# module_Rn_reg.net
KiCad netlist of a schematic drawn in EAGLE
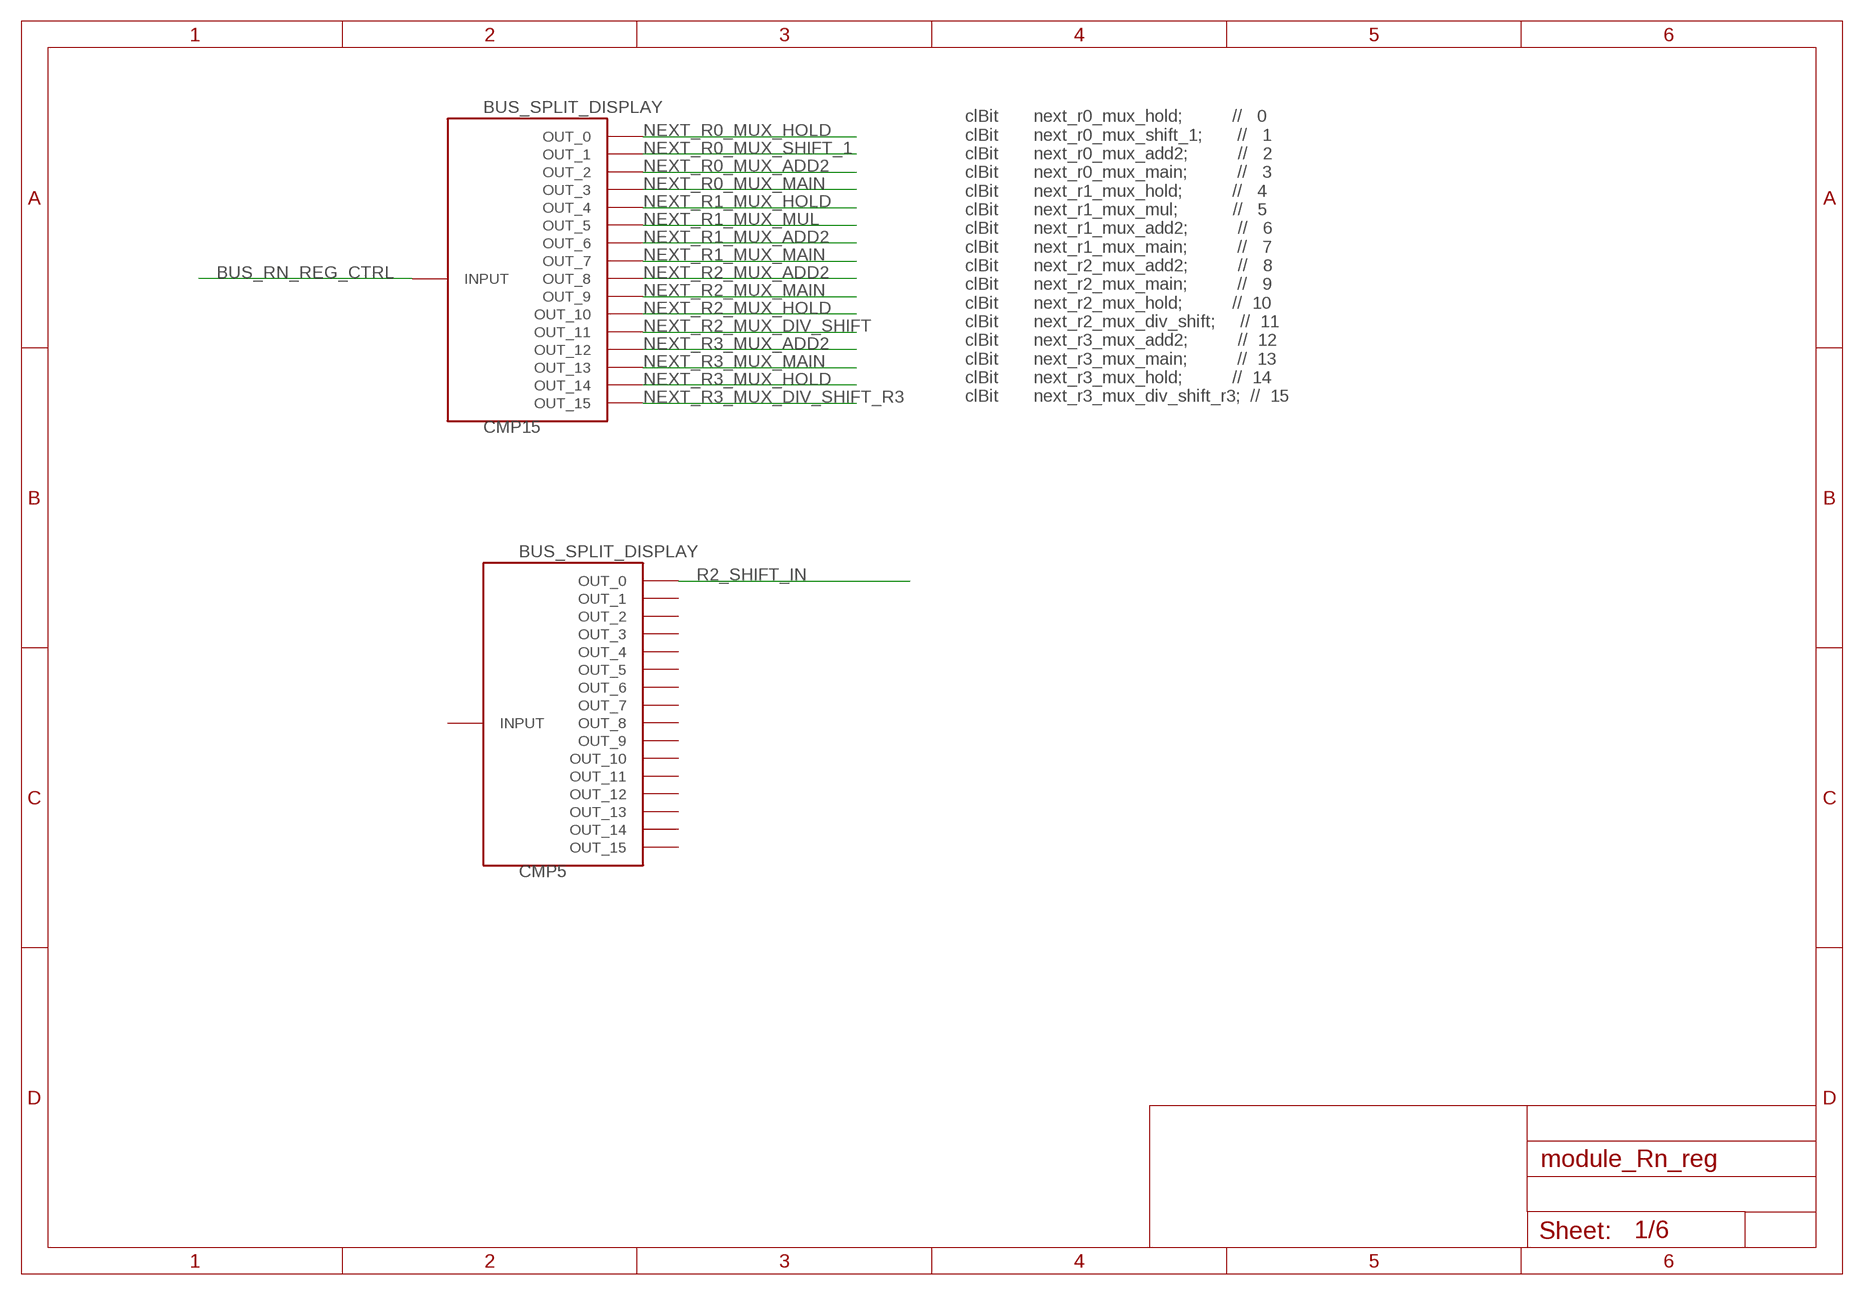
[diagram p0: schematic, sheet 1]
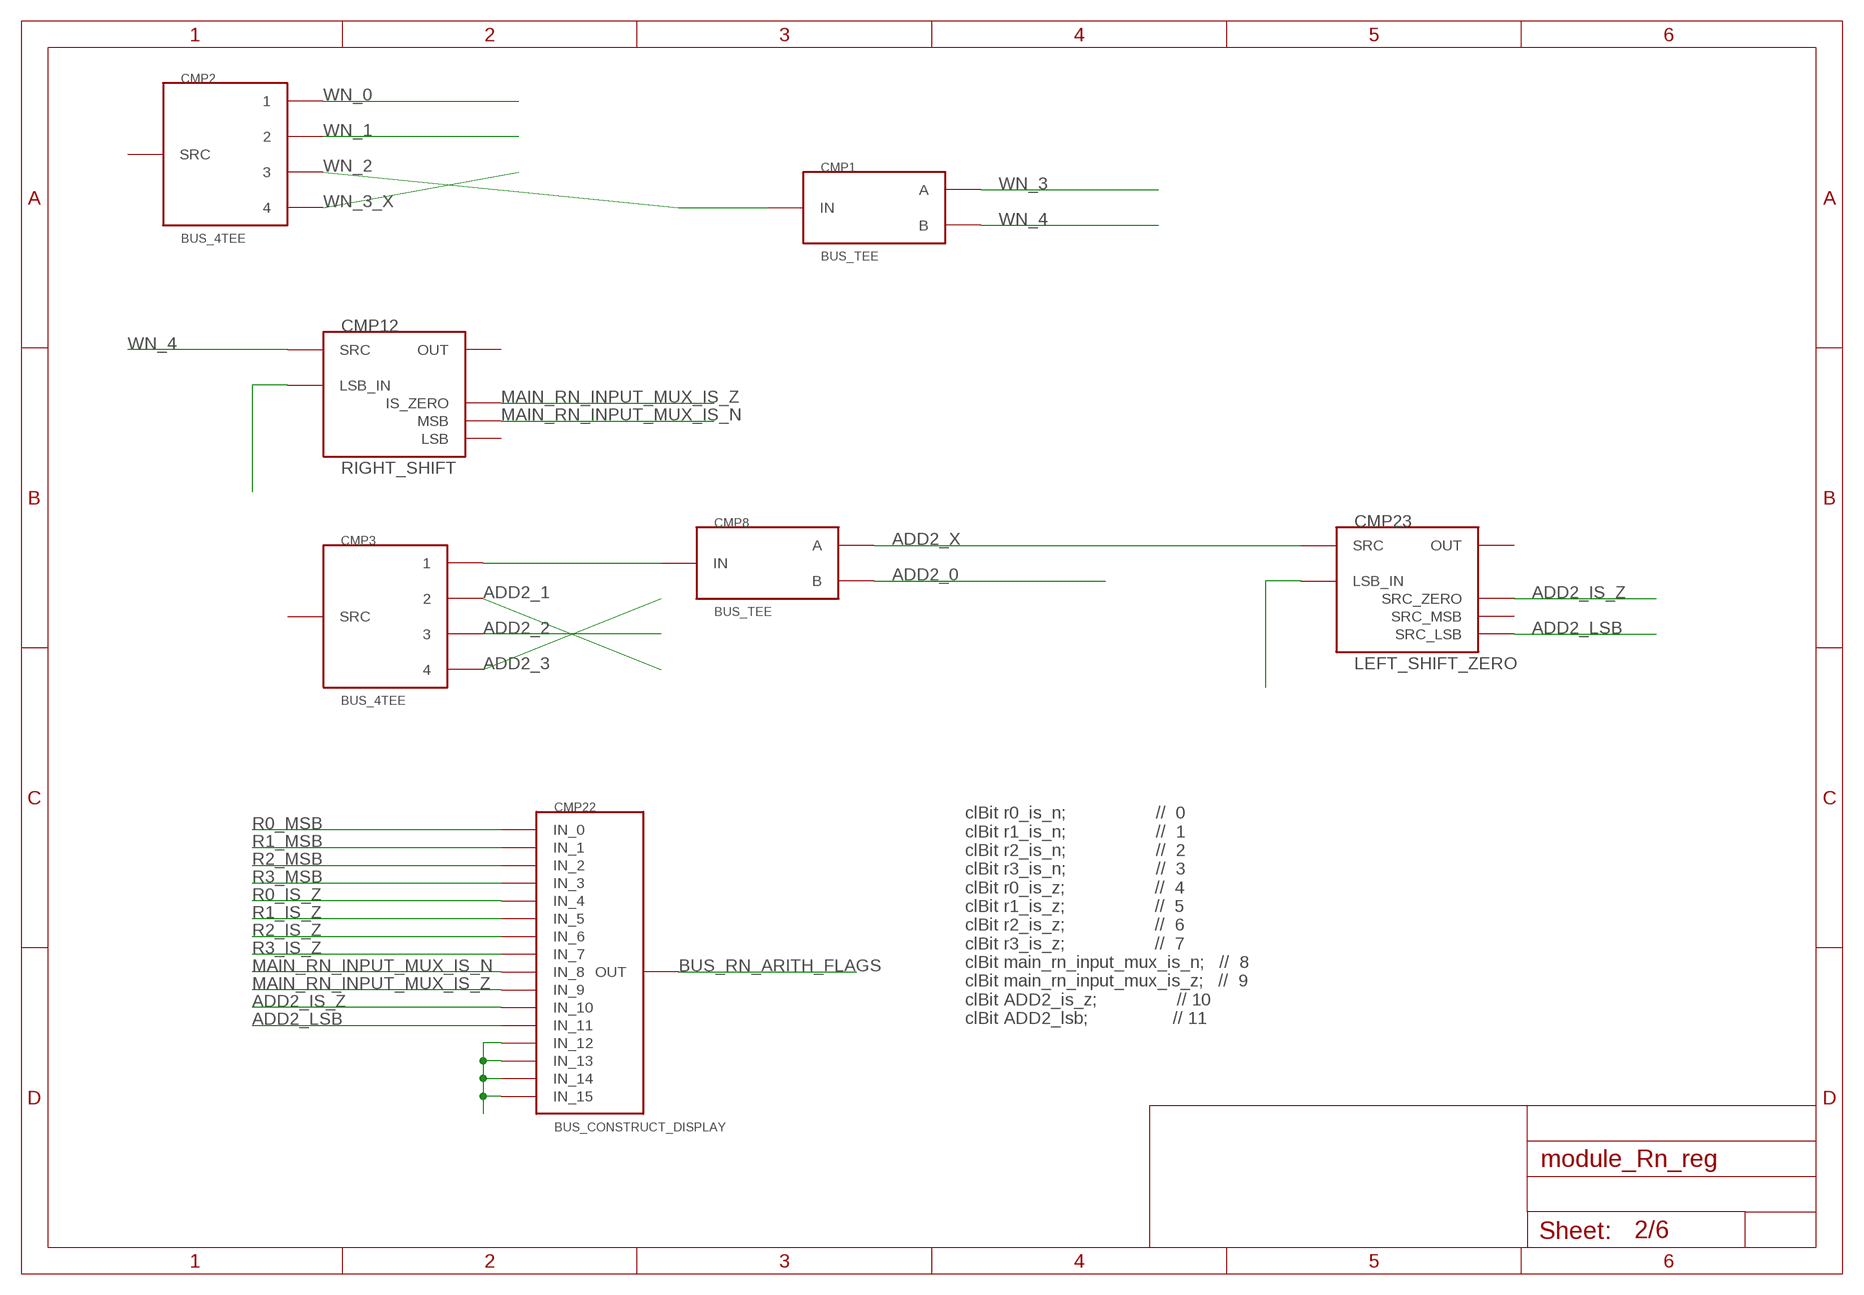
[diagram p1: schematic, sheet 2]
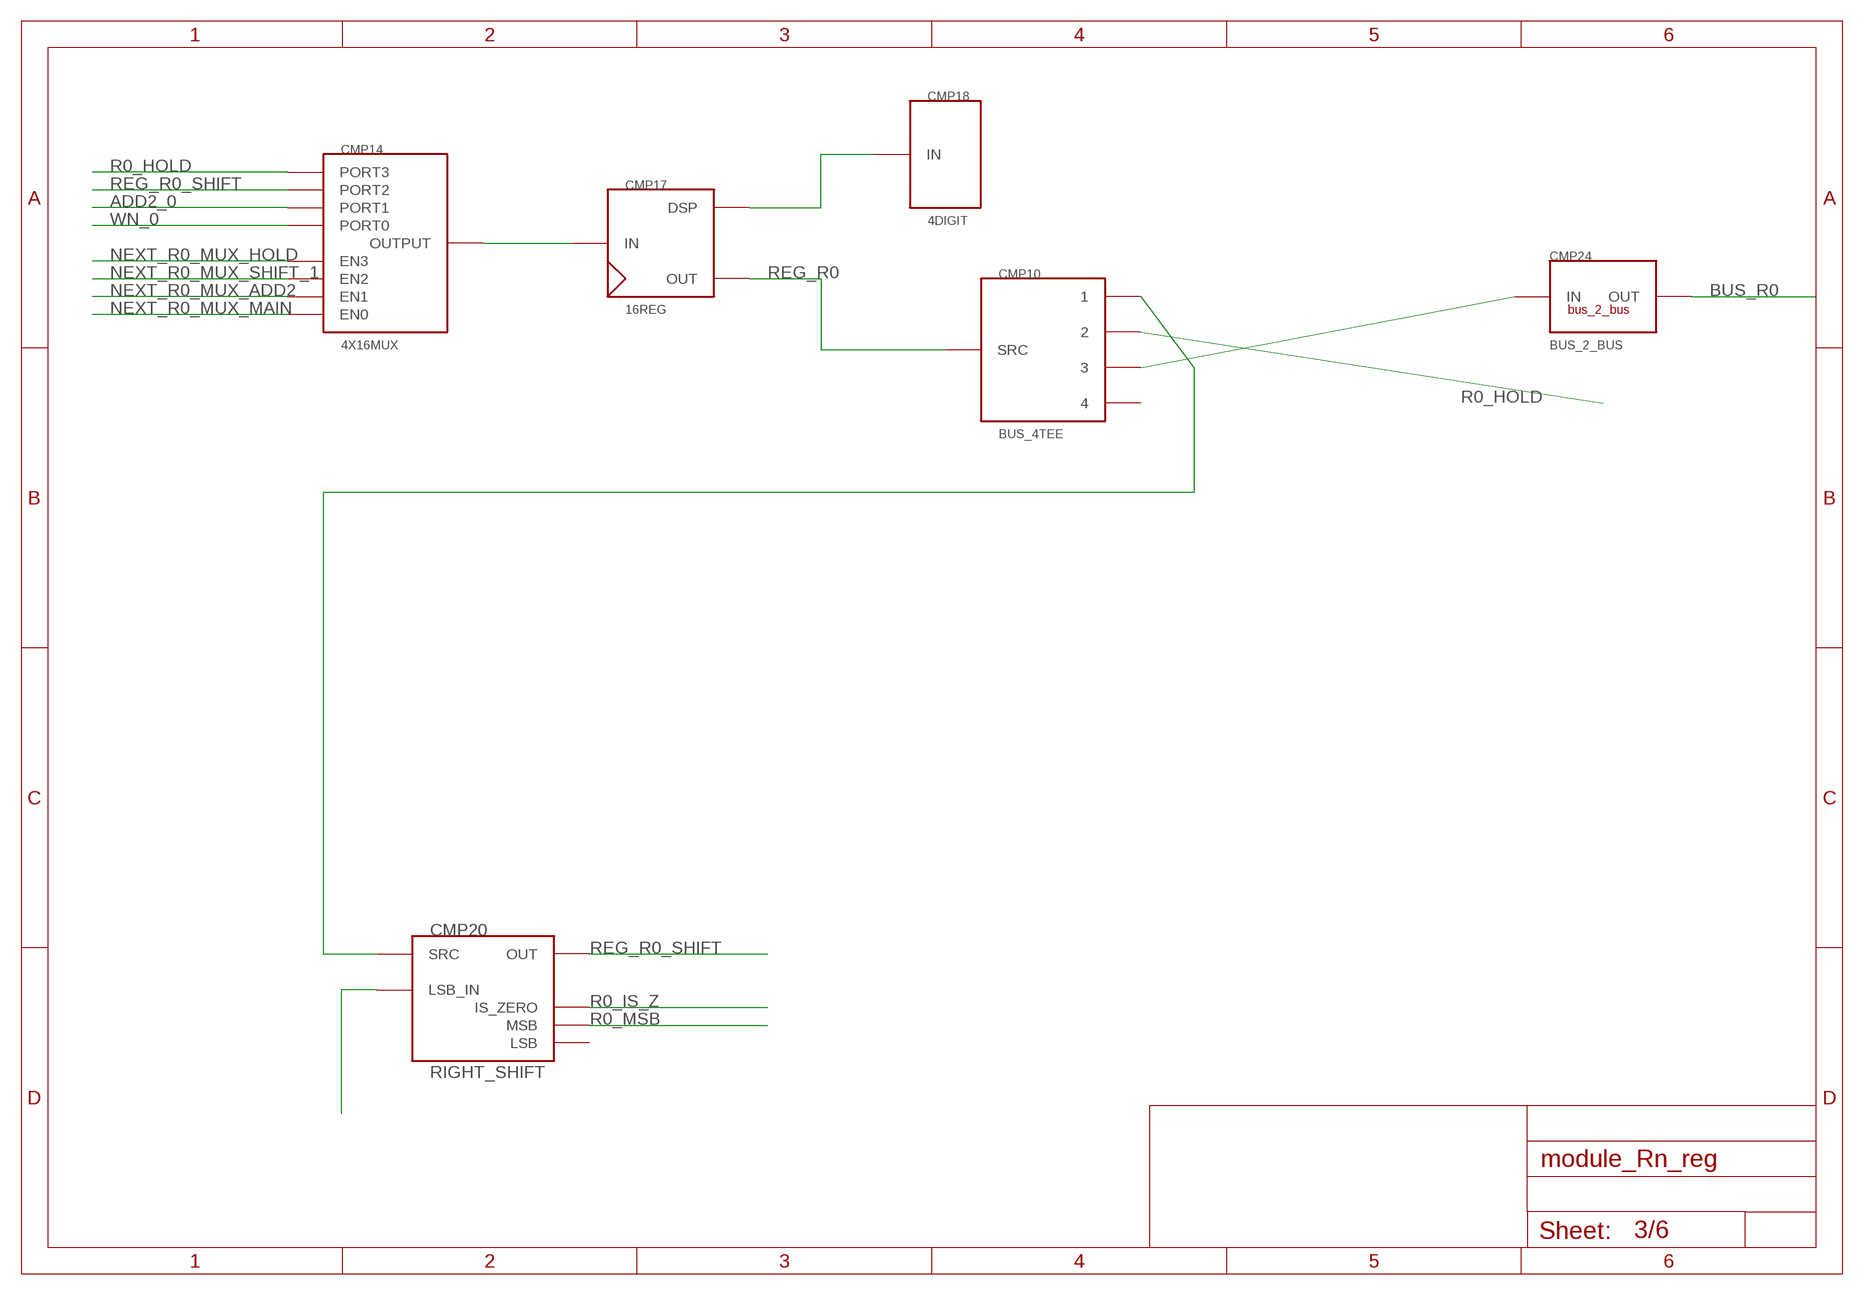
[diagram p2: schematic, sheet 3]
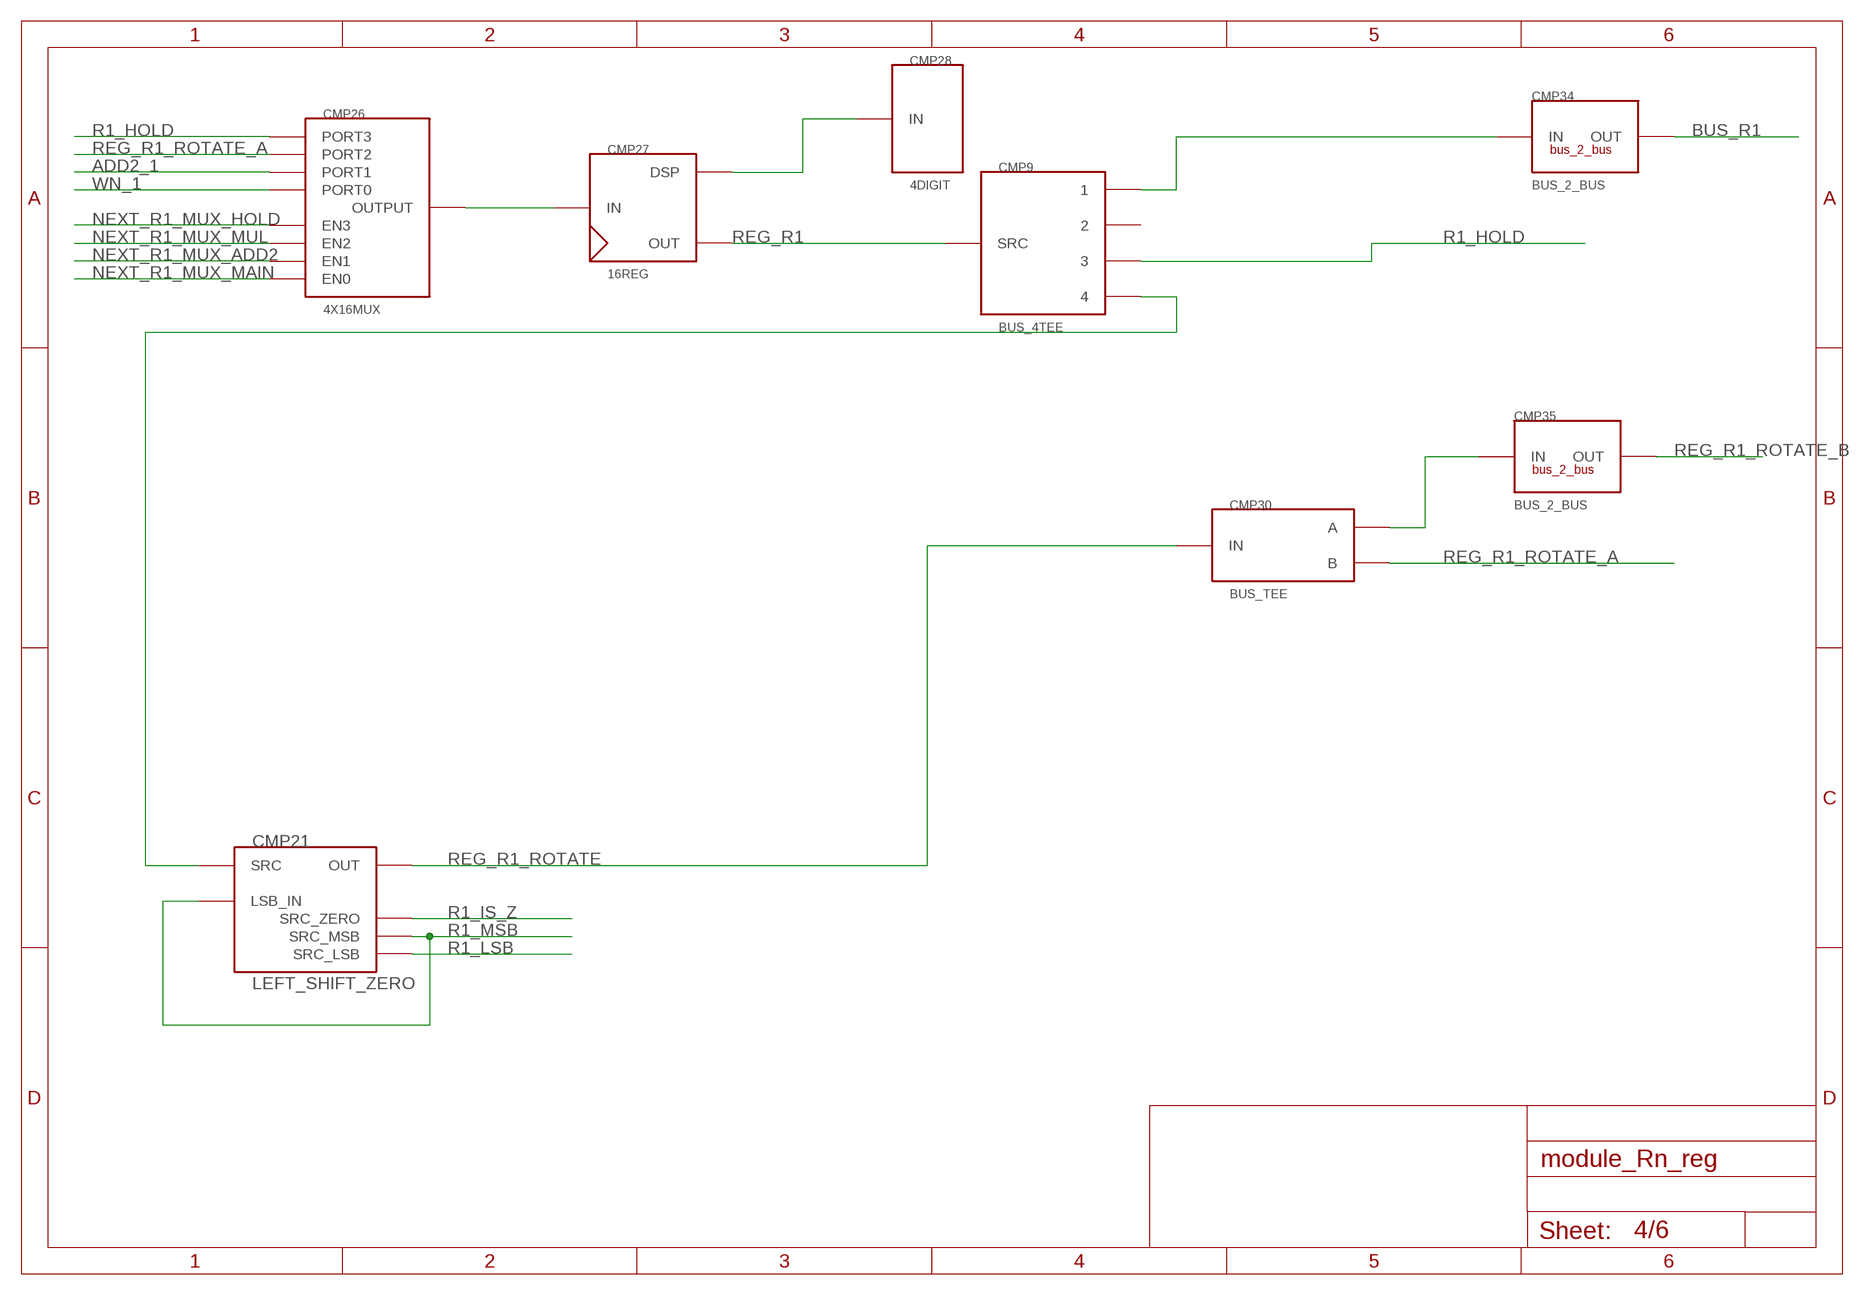
[diagram p3: schematic, sheet 4]
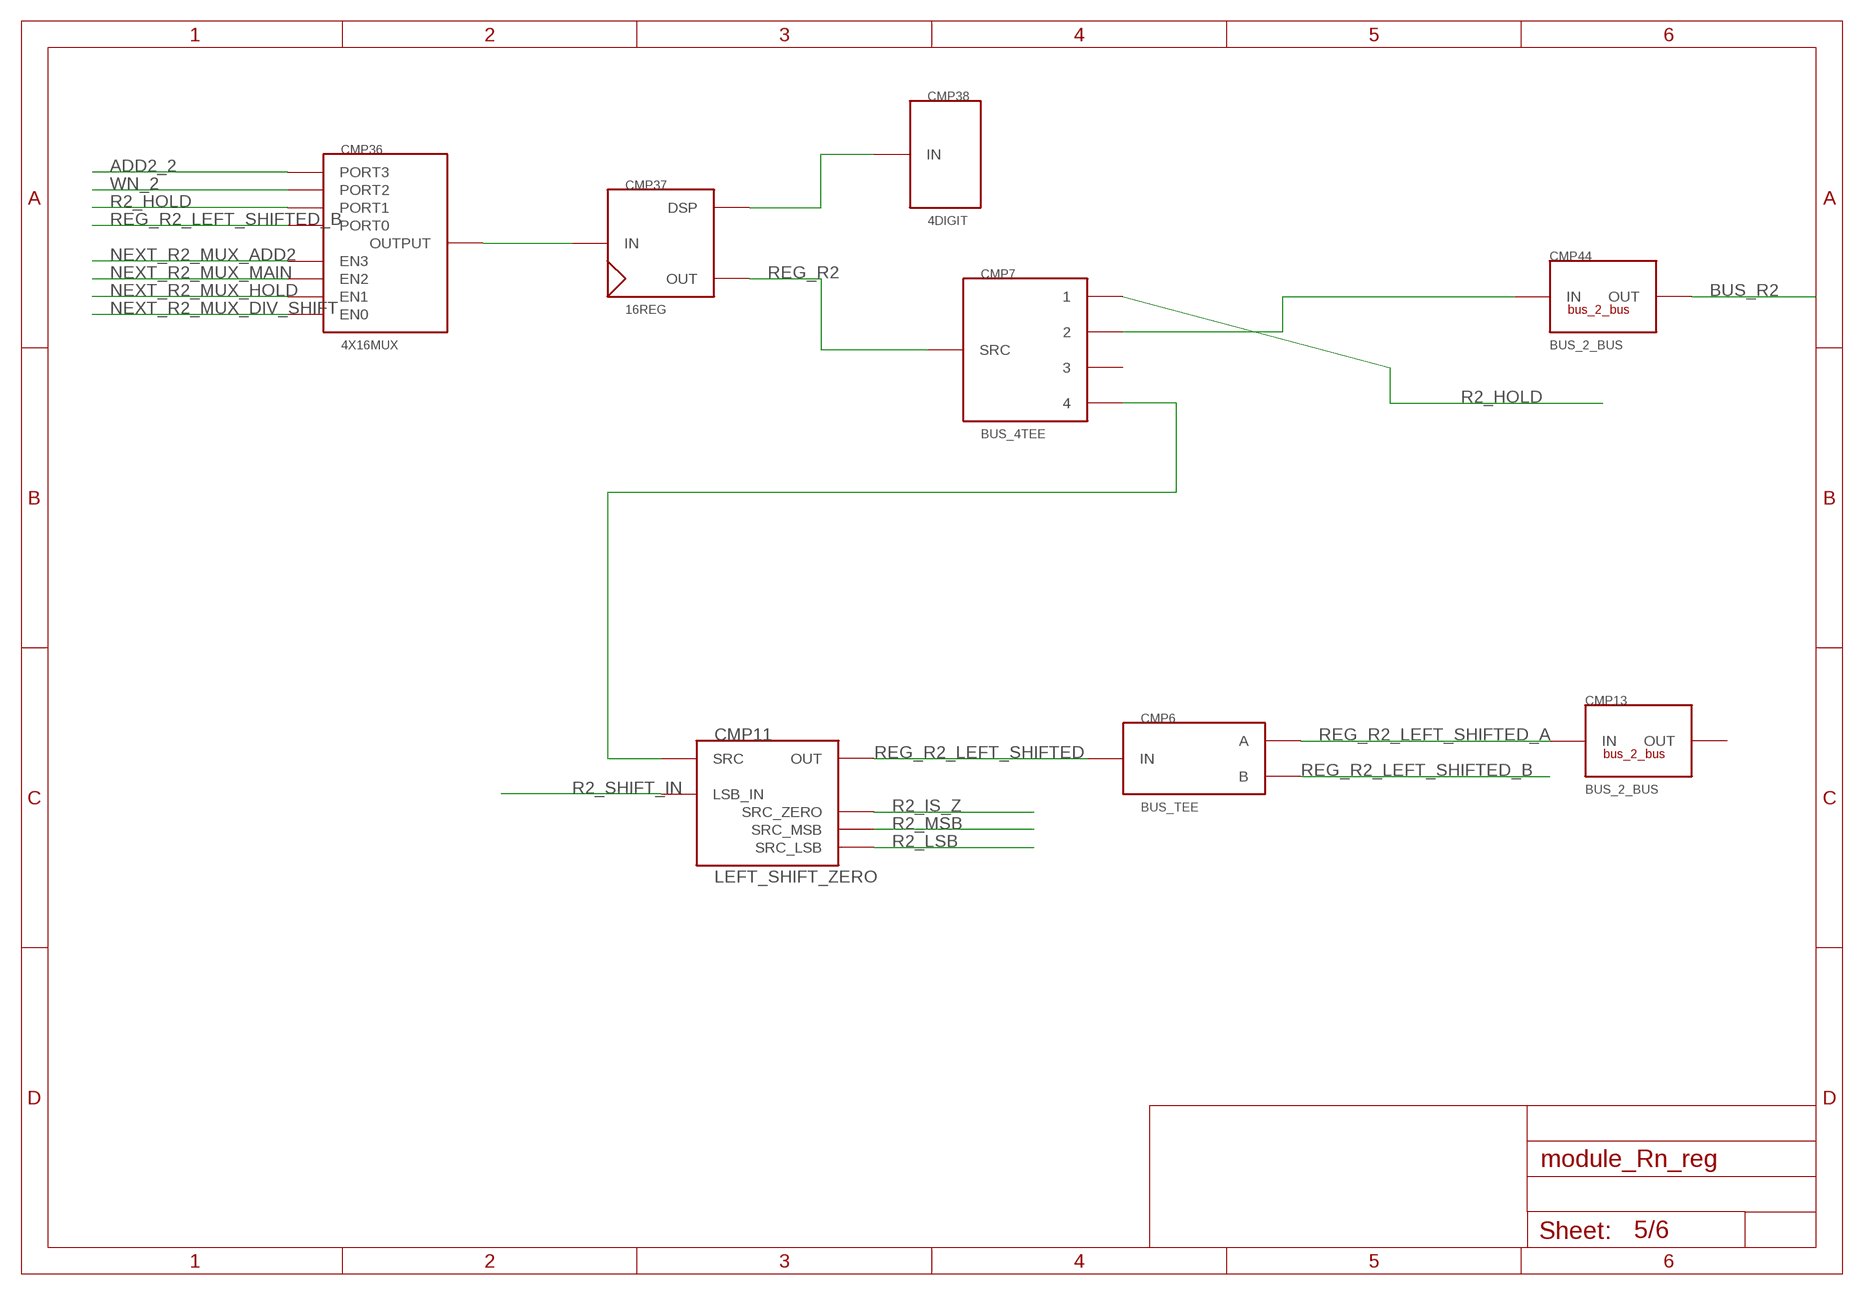
[diagram p4: schematic, sheet 5]
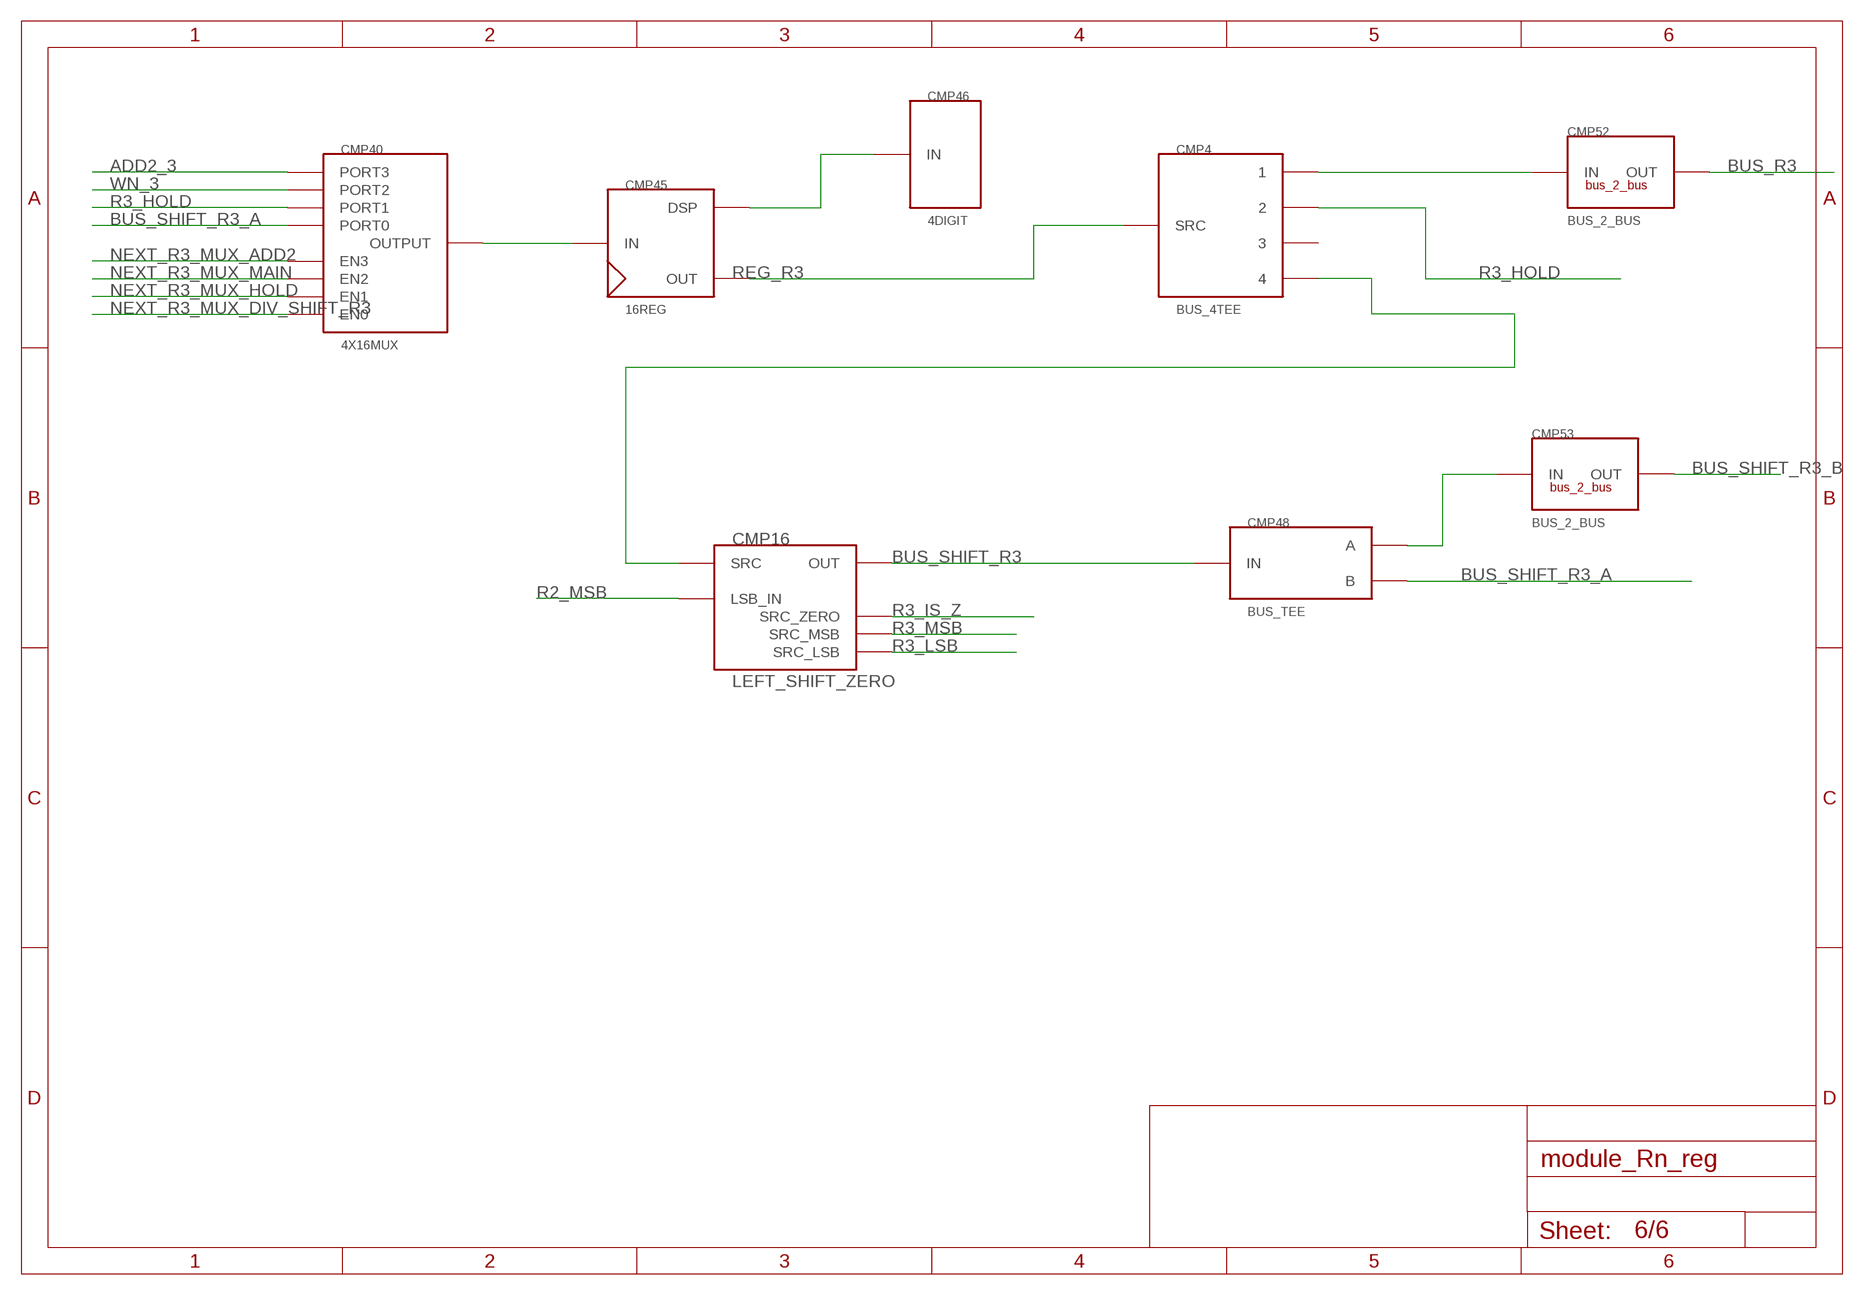
[diagram p5: schematic, sheet 6]

(export (version "E")
  (design (tool "Eeschema 10.0.6"))
  (components
    (comp (ref "CMP1")
      (value "BUS_TEE")
      (footprint "eagle-import:BUS_TEE")
      (libsource (lib "eagle-import") (part "BUS_TEE"))
    )
    (comp (ref "CMP2")
      (value "BUS_4TEE")
      (footprint "eagle-import:BUS_4TEE")
      (libsource (lib "eagle-import") (part "BUS_4TEE"))
    )
    (comp (ref "CMP3")
      (value "BUS_4TEE")
      (footprint "eagle-import:BUS_4TEE")
      (libsource (lib "eagle-import") (part "BUS_4TEE"))
    )
    (comp (ref "CMP8")
      (value "BUS_TEE")
      (footprint "eagle-import:BUS_TEE")
      (libsource (lib "eagle-import") (part "BUS_TEE"))
    )
    (comp (ref "CMP12")
      (value "RIGHT_SHIFT")
      (footprint "eagle-import:SHIFT_ZERO")
      (libsource (lib "eagle-import") (part "RIGHT_SHIFT"))
    )
    (comp (ref "CMP22")
      (value "BUS_CONSTRUCT_DISPLAY")
      (footprint "eagle-import:BUS_SPLIT_DISPLAY")
      (libsource (lib "eagle-import") (part "BUS_CONSTRUCT_DISPLAY"))
    )
    (comp (ref "CMP23")
      (value "LEFT_SHIFT_ZERO")
      (footprint "eagle-import:SHIFT_ZERO")
      (libsource (lib "eagle-import") (part "LEFT_SHIFT_ZERO"))
    )
    (comp (ref "CMP4")
      (value "BUS_4TEE")
      (footprint "eagle-import:BUS_4TEE")
      (libsource (lib "eagle-import") (part "BUS_4TEE"))
    )
    (comp (ref "CMP16")
      (value "LEFT_SHIFT_ZERO")
      (footprint "eagle-import:SHIFT_ZERO")
      (libsource (lib "eagle-import") (part "LEFT_SHIFT_ZERO"))
    )
    (comp (ref "CMP40")
      (value "4X16MUX")
      (footprint "eagle-import:4X16MUX")
      (libsource (lib "eagle-import") (part "4X16MUX"))
    )
    (comp (ref "CMP45")
      (value "16REG")
      (footprint "eagle-import:16REG")
      (libsource (lib "eagle-import") (part "16REG"))
    )
    (comp (ref "CMP46")
      (value "4DIGIT")
      (footprint "eagle-import:4DIGIT")
      (libsource (lib "eagle-import") (part "4DIGIT"))
    )
    (comp (ref "CMP48")
      (value "BUS_TEE")
      (footprint "eagle-import:BUS_TEE")
      (libsource (lib "eagle-import") (part "BUS_TEE"))
    )
    (comp (ref "CMP52")
      (value "BUS_2_BUS")
      (footprint "eagle-import:BUS2BUS")
      (libsource (lib "eagle-import") (part "BUS_2_BUS"))
    )
    (comp (ref "CMP53")
      (value "BUS_2_BUS")
      (footprint "eagle-import:BUS2BUS")
      (libsource (lib "eagle-import") (part "BUS_2_BUS"))
    )
    (comp (ref "CMP9")
      (value "BUS_4TEE")
      (footprint "eagle-import:BUS_4TEE")
      (libsource (lib "eagle-import") (part "BUS_4TEE"))
    )
    (comp (ref "CMP21")
      (value "LEFT_SHIFT_ZERO")
      (footprint "eagle-import:SHIFT_ZERO")
      (libsource (lib "eagle-import") (part "LEFT_SHIFT_ZERO"))
    )
    (comp (ref "CMP26")
      (value "4X16MUX")
      (footprint "eagle-import:4X16MUX")
      (libsource (lib "eagle-import") (part "4X16MUX"))
    )
    (comp (ref "CMP27")
      (value "16REG")
      (footprint "eagle-import:16REG")
      (libsource (lib "eagle-import") (part "16REG"))
    )
    (comp (ref "CMP28")
      (value "4DIGIT")
      (footprint "eagle-import:4DIGIT")
      (libsource (lib "eagle-import") (part "4DIGIT"))
    )
    (comp (ref "CMP30")
      (value "BUS_TEE")
      (footprint "eagle-import:BUS_TEE")
      (libsource (lib "eagle-import") (part "BUS_TEE"))
    )
    (comp (ref "CMP34")
      (value "BUS_2_BUS")
      (footprint "eagle-import:BUS2BUS")
      (libsource (lib "eagle-import") (part "BUS_2_BUS"))
    )
    (comp (ref "CMP35")
      (value "BUS_2_BUS")
      (footprint "eagle-import:BUS2BUS")
      (libsource (lib "eagle-import") (part "BUS_2_BUS"))
    )
    (comp (ref "CMP10")
      (value "BUS_4TEE")
      (footprint "eagle-import:BUS_4TEE")
      (libsource (lib "eagle-import") (part "BUS_4TEE"))
    )
    (comp (ref "CMP14")
      (value "4X16MUX")
      (footprint "eagle-import:4X16MUX")
      (libsource (lib "eagle-import") (part "4X16MUX"))
    )
    (comp (ref "CMP17")
      (value "16REG")
      (footprint "eagle-import:16REG")
      (libsource (lib "eagle-import") (part "16REG"))
    )
    (comp (ref "CMP18")
      (value "4DIGIT")
      (footprint "eagle-import:4DIGIT")
      (libsource (lib "eagle-import") (part "4DIGIT"))
    )
    (comp (ref "CMP20")
      (value "RIGHT_SHIFT")
      (footprint "eagle-import:SHIFT_ZERO")
      (libsource (lib "eagle-import") (part "RIGHT_SHIFT"))
    )
    (comp (ref "CMP24")
      (value "BUS_2_BUS")
      (footprint "eagle-import:BUS2BUS")
      (libsource (lib "eagle-import") (part "BUS_2_BUS"))
    )
    (comp (ref "CMP6")
      (value "BUS_TEE")
      (footprint "eagle-import:BUS_TEE")
      (libsource (lib "eagle-import") (part "BUS_TEE"))
    )
    (comp (ref "CMP7")
      (value "BUS_4TEE")
      (footprint "eagle-import:BUS_4TEE")
      (libsource (lib "eagle-import") (part "BUS_4TEE"))
    )
    (comp (ref "CMP11")
      (value "LEFT_SHIFT_ZERO")
      (footprint "eagle-import:SHIFT_ZERO")
      (libsource (lib "eagle-import") (part "LEFT_SHIFT_ZERO"))
    )
    (comp (ref "CMP13")
      (value "BUS_2_BUS")
      (footprint "eagle-import:BUS2BUS")
      (libsource (lib "eagle-import") (part "BUS_2_BUS"))
    )
    (comp (ref "CMP36")
      (value "4X16MUX")
      (footprint "eagle-import:4X16MUX")
      (libsource (lib "eagle-import") (part "4X16MUX"))
    )
    (comp (ref "CMP37")
      (value "16REG")
      (footprint "eagle-import:16REG")
      (libsource (lib "eagle-import") (part "16REG"))
    )
    (comp (ref "CMP38")
      (value "4DIGIT")
      (footprint "eagle-import:4DIGIT")
      (libsource (lib "eagle-import") (part "4DIGIT"))
    )
    (comp (ref "CMP44")
      (value "BUS_2_BUS")
      (footprint "eagle-import:BUS2BUS")
      (libsource (lib "eagle-import") (part "BUS_2_BUS"))
    )
    (comp (ref "CMP5")
      (value "BUS_SPLIT_DISPLAY")
      (footprint "eagle-import:BUS_SPLIT_DISPLAY")
      (libsource (lib "eagle-import") (part "BUS_SPLIT_DISPLAY"))
    )
    (comp (ref "CMP15")
      (value "BUS_SPLIT_DISPLAY")
      (footprint "eagle-import:BUS_SPLIT_DISPLAY")
      (libsource (lib "eagle-import") (part "BUS_SPLIT_DISPLAY"))
    )
  )
  (nets
    (net (code "1") (name "ADD2_0") (class "Default")
      (node (ref "CMP14") (pin "PORT1") (pinfunction "PORT1_PORT1") (pintype "input"))
      (node (ref "CMP8") (pin "OUTB") (pinfunction "B_OUTB") (pintype "output"))
    )
    (net (code "2") (name "ADD2_1") (class "Default")
      (node (ref "CMP26") (pin "PORT1") (pinfunction "PORT1_PORT1") (pintype "input"))
      (node (ref "CMP3") (pin "4") (pinfunction "4_4") (pintype "output"))
    )
    (net (code "3") (name "ADD2_2") (class "Default")
      (node (ref "CMP3") (pin "3") (pinfunction "3_3") (pintype "output"))
      (node (ref "CMP36") (pin "PORT3") (pinfunction "PORT3_PORT3") (pintype "input"))
    )
    (net (code "4") (name "ADD2_3") (class "Default")
      (node (ref "CMP3") (pin "2") (pinfunction "2_2") (pintype "output"))
      (node (ref "CMP40") (pin "PORT3") (pinfunction "PORT3_PORT3") (pintype "input"))
    )
    (net (code "5") (name "ADD2_IS_Z") (class "Default")
      (node (ref "CMP22") (pin "P$11") (pinfunction "IN_10_P$11") (pintype "input"))
      (node (ref "CMP23") (pin "IS_ZERO") (pinfunction "SRC_ZERO_IS_ZERO") (pintype "output"))
    )
    (net (code "6") (name "ADD2_LSB") (class "Default")
      (node (ref "CMP22") (pin "P$12") (pinfunction "IN_11_P$12") (pintype "input"))
      (node (ref "CMP23") (pin "LSB") (pinfunction "SRC_LSB_LSB") (pintype "output"))
    )
    (net (code "7") (name "ADD2_X") (class "Default")
      (node (ref "CMP23") (pin "LSRC") (pinfunction "SRC_LSRC") (pintype "input"))
      (node (ref "CMP8") (pin "OUT_A") (pinfunction "A_OUT_A") (pintype "output"))
    )
    (net (code "8") (name "BUS_R0") (class "Default")
      (node (ref "CMP24") (pin "P$2") (pinfunction "OUT_P$2") (pintype "output"))
    )
    (net (code "9") (name "BUS_R1") (class "Default")
      (node (ref "CMP34") (pin "P$2") (pinfunction "OUT_P$2") (pintype "output"))
    )
    (net (code "10") (name "BUS_R2") (class "Default")
      (node (ref "CMP44") (pin "P$2") (pinfunction "OUT_P$2") (pintype "output"))
    )
    (net (code "11") (name "BUS_R3") (class "Default")
      (node (ref "CMP52") (pin "P$2") (pinfunction "OUT_P$2") (pintype "output"))
    )
    (net (code "12") (name "BUS_RN_ARITH_FLAGS") (class "Default")
      (node (ref "CMP22") (pin "INPUT") (pinfunction "OUT_INPUT") (pintype "output"))
    )
    (net (code "13") (name "BUS_RN_REG_CTRL") (class "Default")
      (node (ref "CMP15") (pin "INPUT") (pinfunction "INPUT_INPUT") (pintype "input"))
    )
    (net (code "14") (name "BUS_SHIFT_R3") (class "Default")
      (node (ref "CMP16") (pin "RSRC") (pinfunction "OUT_RSRC") (pintype "output"))
      (node (ref "CMP48") (pin "INPUT") (pinfunction "IN_INPUT") (pintype "input"))
    )
    (net (code "15") (name "BUS_SHIFT_R3_A") (class "Default")
      (node (ref "CMP40") (pin "PORT0") (pinfunction "PORT0_PORT0") (pintype "input"))
      (node (ref "CMP48") (pin "OUTB") (pinfunction "B_OUTB") (pintype "output"))
    )
    (net (code "16") (name "BUS_SHIFT_R3_B") (class "Default")
      (node (ref "CMP53") (pin "P$2") (pinfunction "OUT_P$2") (pintype "output"))
    )
    (net (code "17") (name "MAIN_RN_INPUT_MUX_IS_N") (class "Default")
      (node (ref "CMP12") (pin "MSB") (pinfunction "MSB_MSB") (pintype "output"))
      (node (ref "CMP22") (pin "P$9") (pinfunction "IN_8_P$9") (pintype "input"))
    )
    (net (code "18") (name "MAIN_RN_INPUT_MUX_IS_Z") (class "Default")
      (node (ref "CMP12") (pin "IS_ZERO") (pinfunction "IS_ZERO_IS_ZERO") (pintype "output"))
      (node (ref "CMP22") (pin "P$10") (pinfunction "IN_9_P$10") (pintype "input"))
    )
    (net (code "19") (name "NEXT_R0_MUX_ADD2") (class "Default")
      (node (ref "CMP14") (pin "EN1") (pinfunction "EN1_EN1") (pintype "input"))
      (node (ref "CMP15") (pin "P$3") (pinfunction "OUT_2_P$3") (pintype "output"))
    )
    (net (code "20") (name "NEXT_R0_MUX_HOLD") (class "Default")
      (node (ref "CMP14") (pin "EN3") (pinfunction "EN3_EN3") (pintype "input"))
      (node (ref "CMP15") (pin "P$1") (pinfunction "OUT_0_P$1") (pintype "output"))
    )
    (net (code "21") (name "NEXT_R0_MUX_MAIN") (class "Default")
      (node (ref "CMP14") (pin "EN0") (pinfunction "EN0_EN0") (pintype "input"))
      (node (ref "CMP15") (pin "P$4") (pinfunction "OUT_3_P$4") (pintype "output"))
    )
    (net (code "22") (name "NEXT_R0_MUX_SHIFT_1") (class "Default")
      (node (ref "CMP14") (pin "EN2") (pinfunction "EN2_EN2") (pintype "input"))
      (node (ref "CMP15") (pin "P$2") (pinfunction "OUT_1_P$2") (pintype "output"))
    )
    (net (code "23") (name "NEXT_R1_MUX_ADD2") (class "Default")
      (node (ref "CMP15") (pin "P$7") (pinfunction "OUT_6_P$7") (pintype "output"))
      (node (ref "CMP26") (pin "EN1") (pinfunction "EN1_EN1") (pintype "input"))
    )
    (net (code "24") (name "NEXT_R1_MUX_HOLD") (class "Default")
      (node (ref "CMP15") (pin "P$5") (pinfunction "OUT_4_P$5") (pintype "output"))
      (node (ref "CMP26") (pin "EN3") (pinfunction "EN3_EN3") (pintype "input"))
    )
    (net (code "25") (name "NEXT_R1_MUX_MAIN") (class "Default")
      (node (ref "CMP15") (pin "P$8") (pinfunction "OUT_7_P$8") (pintype "output"))
      (node (ref "CMP26") (pin "EN0") (pinfunction "EN0_EN0") (pintype "input"))
    )
    (net (code "26") (name "NEXT_R1_MUX_MUL") (class "Default")
      (node (ref "CMP15") (pin "P$6") (pinfunction "OUT_5_P$6") (pintype "output"))
      (node (ref "CMP26") (pin "EN2") (pinfunction "EN2_EN2") (pintype "input"))
    )
    (net (code "27") (name "NEXT_R2_MUX_ADD2") (class "Default")
      (node (ref "CMP15") (pin "P$9") (pinfunction "OUT_8_P$9") (pintype "output"))
      (node (ref "CMP36") (pin "EN3") (pinfunction "EN3_EN3") (pintype "input"))
    )
    (net (code "28") (name "NEXT_R2_MUX_DIV_SHIFT") (class "Default")
      (node (ref "CMP15") (pin "P$12") (pinfunction "OUT_11_P$12") (pintype "output"))
      (node (ref "CMP36") (pin "EN0") (pinfunction "EN0_EN0") (pintype "input"))
    )
    (net (code "29") (name "NEXT_R2_MUX_HOLD") (class "Default")
      (node (ref "CMP15") (pin "P$11") (pinfunction "OUT_10_P$11") (pintype "output"))
      (node (ref "CMP36") (pin "EN1") (pinfunction "EN1_EN1") (pintype "input"))
    )
    (net (code "30") (name "NEXT_R2_MUX_MAIN") (class "Default")
      (node (ref "CMP15") (pin "P$10") (pinfunction "OUT_9_P$10") (pintype "output"))
      (node (ref "CMP36") (pin "EN2") (pinfunction "EN2_EN2") (pintype "input"))
    )
    (net (code "31") (name "NEXT_R3_MUX_ADD2") (class "Default")
      (node (ref "CMP15") (pin "P$13") (pinfunction "OUT_12_P$13") (pintype "output"))
      (node (ref "CMP40") (pin "EN3") (pinfunction "EN3_EN3") (pintype "input"))
    )
    (net (code "32") (name "NEXT_R3_MUX_DIV_SHIFT_R3") (class "Default")
      (node (ref "CMP15") (pin "P$16") (pinfunction "OUT_15_P$16") (pintype "output"))
      (node (ref "CMP40") (pin "EN0") (pinfunction "EN0_EN0") (pintype "input"))
    )
    (net (code "33") (name "NEXT_R3_MUX_HOLD") (class "Default")
      (node (ref "CMP15") (pin "P$15") (pinfunction "OUT_14_P$15") (pintype "output"))
      (node (ref "CMP40") (pin "EN1") (pinfunction "EN1_EN1") (pintype "input"))
    )
    (net (code "34") (name "NEXT_R3_MUX_MAIN") (class "Default")
      (node (ref "CMP15") (pin "P$14") (pinfunction "OUT_13_P$14") (pintype "output"))
      (node (ref "CMP40") (pin "EN2") (pinfunction "EN2_EN2") (pintype "input"))
    )
    (net (code "35") (name "Net-(CMP8-IN)") (class "Default")
      (node (ref "CMP3") (pin "1") (pinfunction "1_1") (pintype "output"))
      (node (ref "CMP8") (pin "INPUT") (pinfunction "IN_INPUT") (pintype "input"))
    )
    (net (code "36") (name "Net-(CMP11-SRC)") (class "Default")
      (node (ref "CMP11") (pin "LSRC") (pinfunction "SRC_LSRC") (pintype "input"))
      (node (ref "CMP7") (pin "4") (pinfunction "4_4") (pintype "output"))
    )
    (net (code "37") (name "Net-(CMP14-OUTPUT)") (class "Default")
      (node (ref "CMP14") (pin "PORTOUT") (pinfunction "OUTPUT_PORTOUT") (pintype "output"))
      (node (ref "CMP17") (pin "INPUT") (pinfunction "IN_INPUT") (pintype "input"))
    )
    (net (code "38") (name "Net-(CMP16-SRC)") (class "Default")
      (node (ref "CMP16") (pin "LSRC") (pinfunction "SRC_LSRC") (pintype "input"))
      (node (ref "CMP4") (pin "4") (pinfunction "4_4") (pintype "output"))
    )
    (net (code "39") (name "Net-(CMP17-DSP)") (class "Default")
      (node (ref "CMP17") (pin "DISPLAY") (pinfunction "DSP_DISPLAY") (pintype "output"))
      (node (ref "CMP18") (pin "P$1") (pinfunction "IN_P$1") (pintype "input"))
    )
    (net (code "40") (name "Net-(CMP20-SRC)") (class "Default")
      (node (ref "CMP10") (pin "1") (pinfunction "1_1") (pintype "output"))
      (node (ref "CMP20") (pin "RSRC") (pinfunction "SRC_RSRC") (pintype "input"))
    )
    (net (code "41") (name "Net-(CMP21-SRC)") (class "Default")
      (node (ref "CMP21") (pin "LSRC") (pinfunction "SRC_LSRC") (pintype "input"))
      (node (ref "CMP9") (pin "4") (pinfunction "4_4") (pintype "output"))
    )
    (net (code "42") (name "Net-(CMP22-IN_12)") (class "Default")
      (node (ref "CMP22") (pin "P$13") (pinfunction "IN_12_P$13") (pintype "input"))
      (node (ref "CMP22") (pin "P$14") (pinfunction "IN_13_P$14") (pintype "input"))
      (node (ref "CMP22") (pin "P$15") (pinfunction "IN_14_P$15") (pintype "input"))
      (node (ref "CMP22") (pin "P$16") (pinfunction "IN_15_P$16") (pintype "input"))
    )
    (net (code "43") (name "Net-(CMP24-IN)") (class "Default")
      (node (ref "CMP10") (pin "3") (pinfunction "3_3") (pintype "output"))
      (node (ref "CMP24") (pin "P$1") (pinfunction "IN_P$1") (pintype "input"))
    )
    (net (code "44") (name "Net-(CMP26-OUTPUT)") (class "Default")
      (node (ref "CMP26") (pin "PORTOUT") (pinfunction "OUTPUT_PORTOUT") (pintype "output"))
      (node (ref "CMP27") (pin "INPUT") (pinfunction "IN_INPUT") (pintype "input"))
    )
    (net (code "45") (name "Net-(CMP27-DSP)") (class "Default")
      (node (ref "CMP27") (pin "DISPLAY") (pinfunction "DSP_DISPLAY") (pintype "output"))
      (node (ref "CMP28") (pin "P$1") (pinfunction "IN_P$1") (pintype "input"))
    )
    (net (code "46") (name "Net-(CMP30-A)") (class "Default")
      (node (ref "CMP30") (pin "OUT_A") (pinfunction "A_OUT_A") (pintype "output"))
      (node (ref "CMP35") (pin "P$1") (pinfunction "IN_P$1") (pintype "input"))
    )
    (net (code "47") (name "Net-(CMP34-IN)") (class "Default")
      (node (ref "CMP34") (pin "P$1") (pinfunction "IN_P$1") (pintype "input"))
      (node (ref "CMP9") (pin "1") (pinfunction "1_1") (pintype "output"))
    )
    (net (code "48") (name "Net-(CMP36-OUTPUT)") (class "Default")
      (node (ref "CMP36") (pin "PORTOUT") (pinfunction "OUTPUT_PORTOUT") (pintype "output"))
      (node (ref "CMP37") (pin "INPUT") (pinfunction "IN_INPUT") (pintype "input"))
    )
    (net (code "49") (name "Net-(CMP37-DSP)") (class "Default")
      (node (ref "CMP37") (pin "DISPLAY") (pinfunction "DSP_DISPLAY") (pintype "output"))
      (node (ref "CMP38") (pin "P$1") (pinfunction "IN_P$1") (pintype "input"))
    )
    (net (code "50") (name "Net-(CMP40-OUTPUT)") (class "Default")
      (node (ref "CMP40") (pin "PORTOUT") (pinfunction "OUTPUT_PORTOUT") (pintype "output"))
      (node (ref "CMP45") (pin "INPUT") (pinfunction "IN_INPUT") (pintype "input"))
    )
    (net (code "51") (name "Net-(CMP44-IN)") (class "Default")
      (node (ref "CMP44") (pin "P$1") (pinfunction "IN_P$1") (pintype "input"))
      (node (ref "CMP7") (pin "2") (pinfunction "2_2") (pintype "output"))
    )
    (net (code "52") (name "Net-(CMP45-DSP)") (class "Default")
      (node (ref "CMP45") (pin "DISPLAY") (pinfunction "DSP_DISPLAY") (pintype "output"))
      (node (ref "CMP46") (pin "P$1") (pinfunction "IN_P$1") (pintype "input"))
    )
    (net (code "53") (name "Net-(CMP48-A)") (class "Default")
      (node (ref "CMP48") (pin "OUT_A") (pinfunction "A_OUT_A") (pintype "output"))
      (node (ref "CMP53") (pin "P$1") (pinfunction "IN_P$1") (pintype "input"))
    )
    (net (code "54") (name "Net-(CMP52-IN)") (class "Default")
      (node (ref "CMP4") (pin "1") (pinfunction "1_1") (pintype "output"))
      (node (ref "CMP52") (pin "P$1") (pinfunction "IN_P$1") (pintype "input"))
    )
    (net (code "55") (name "R0_HOLD") (class "Default")
      (node (ref "CMP10") (pin "2") (pinfunction "2_2") (pintype "output"))
      (node (ref "CMP14") (pin "PORT3") (pinfunction "PORT3_PORT3") (pintype "input"))
    )
    (net (code "56") (name "R0_IS_Z") (class "Default")
      (node (ref "CMP20") (pin "IS_ZERO") (pinfunction "IS_ZERO_IS_ZERO") (pintype "output"))
      (node (ref "CMP22") (pin "P$5") (pinfunction "IN_4_P$5") (pintype "input"))
    )
    (net (code "57") (name "R0_MSB") (class "Default")
      (node (ref "CMP20") (pin "MSB") (pinfunction "MSB_MSB") (pintype "output"))
      (node (ref "CMP22") (pin "P$1") (pinfunction "IN_0_P$1") (pintype "input"))
    )
    (net (code "58") (name "R1_HOLD") (class "Default")
      (node (ref "CMP26") (pin "PORT3") (pinfunction "PORT3_PORT3") (pintype "input"))
      (node (ref "CMP9") (pin "3") (pinfunction "3_3") (pintype "output"))
    )
    (net (code "59") (name "R1_IS_Z") (class "Default")
      (node (ref "CMP21") (pin "IS_ZERO") (pinfunction "SRC_ZERO_IS_ZERO") (pintype "output"))
      (node (ref "CMP22") (pin "P$6") (pinfunction "IN_5_P$6") (pintype "input"))
    )
    (net (code "60") (name "R1_LSB") (class "Default")
      (node (ref "CMP21") (pin "LSB") (pinfunction "SRC_LSB_LSB") (pintype "output"))
    )
    (net (code "61") (name "R1_MSB") (class "Default")
      (node (ref "CMP21") (pin "MSB") (pinfunction "SRC_MSB_MSB") (pintype "output"))
      (node (ref "CMP21") (pin "SHIFT_IN") (pinfunction "LSB_IN_SHIFT_IN") (pintype "input"))
      (node (ref "CMP22") (pin "P$2") (pinfunction "IN_1_P$2") (pintype "input"))
    )
    (net (code "62") (name "R2_HOLD") (class "Default")
      (node (ref "CMP36") (pin "PORT1") (pinfunction "PORT1_PORT1") (pintype "input"))
      (node (ref "CMP7") (pin "1") (pinfunction "1_1") (pintype "output"))
    )
    (net (code "63") (name "R2_IS_Z") (class "Default")
      (node (ref "CMP11") (pin "IS_ZERO") (pinfunction "SRC_ZERO_IS_ZERO") (pintype "output"))
      (node (ref "CMP22") (pin "P$7") (pinfunction "IN_6_P$7") (pintype "input"))
    )
    (net (code "64") (name "R2_LSB") (class "Default")
      (node (ref "CMP11") (pin "LSB") (pinfunction "SRC_LSB_LSB") (pintype "output"))
    )
    (net (code "65") (name "R2_MSB") (class "Default")
      (node (ref "CMP11") (pin "MSB") (pinfunction "SRC_MSB_MSB") (pintype "output"))
      (node (ref "CMP16") (pin "SHIFT_IN") (pinfunction "LSB_IN_SHIFT_IN") (pintype "input"))
      (node (ref "CMP22") (pin "P$3") (pinfunction "IN_2_P$3") (pintype "input"))
    )
    (net (code "66") (name "R2_SHIFT_IN") (class "Default")
      (node (ref "CMP11") (pin "SHIFT_IN") (pinfunction "LSB_IN_SHIFT_IN") (pintype "input"))
      (node (ref "CMP5") (pin "P$1") (pinfunction "OUT_0_P$1") (pintype "output"))
    )
    (net (code "67") (name "R3_HOLD") (class "Default")
      (node (ref "CMP4") (pin "2") (pinfunction "2_2") (pintype "output"))
      (node (ref "CMP40") (pin "PORT1") (pinfunction "PORT1_PORT1") (pintype "input"))
    )
    (net (code "68") (name "R3_IS_Z") (class "Default")
      (node (ref "CMP16") (pin "IS_ZERO") (pinfunction "SRC_ZERO_IS_ZERO") (pintype "output"))
      (node (ref "CMP22") (pin "P$8") (pinfunction "IN_7_P$8") (pintype "input"))
    )
    (net (code "69") (name "R3_LSB") (class "Default")
      (node (ref "CMP16") (pin "LSB") (pinfunction "SRC_LSB_LSB") (pintype "output"))
    )
    (net (code "70") (name "R3_MSB") (class "Default")
      (node (ref "CMP16") (pin "MSB") (pinfunction "SRC_MSB_MSB") (pintype "output"))
      (node (ref "CMP22") (pin "P$4") (pinfunction "IN_3_P$4") (pintype "input"))
    )
    (net (code "71") (name "REG_R0") (class "Default")
      (node (ref "CMP10") (pin "SRC") (pinfunction "SRC_SRC") (pintype "input"))
      (node (ref "CMP17") (pin "OUT") (pinfunction "OUT_OUT") (pintype "output"))
    )
    (net (code "72") (name "REG_R0_SHIFT") (class "Default")
      (node (ref "CMP14") (pin "PORT2") (pinfunction "PORT2_PORT2") (pintype "input"))
      (node (ref "CMP20") (pin "LSRC") (pinfunction "OUT_LSRC") (pintype "output"))
    )
    (net (code "73") (name "REG_R1") (class "Default")
      (node (ref "CMP27") (pin "OUT") (pinfunction "OUT_OUT") (pintype "output"))
      (node (ref "CMP9") (pin "SRC") (pinfunction "SRC_SRC") (pintype "input"))
    )
    (net (code "74") (name "REG_R1_ROTATE") (class "Default")
      (node (ref "CMP21") (pin "RSRC") (pinfunction "OUT_RSRC") (pintype "output"))
      (node (ref "CMP30") (pin "INPUT") (pinfunction "IN_INPUT") (pintype "input"))
    )
    (net (code "75") (name "REG_R1_ROTATE_A") (class "Default")
      (node (ref "CMP26") (pin "PORT2") (pinfunction "PORT2_PORT2") (pintype "input"))
      (node (ref "CMP30") (pin "OUTB") (pinfunction "B_OUTB") (pintype "output"))
    )
    (net (code "76") (name "REG_R1_ROTATE_B") (class "Default")
      (node (ref "CMP35") (pin "P$2") (pinfunction "OUT_P$2") (pintype "output"))
    )
    (net (code "77") (name "REG_R2") (class "Default")
      (node (ref "CMP37") (pin "OUT") (pinfunction "OUT_OUT") (pintype "output"))
      (node (ref "CMP7") (pin "SRC") (pinfunction "SRC_SRC") (pintype "input"))
    )
    (net (code "78") (name "REG_R2_LEFT_SHIFTED") (class "Default")
      (node (ref "CMP11") (pin "RSRC") (pinfunction "OUT_RSRC") (pintype "output"))
      (node (ref "CMP6") (pin "INPUT") (pinfunction "IN_INPUT") (pintype "input"))
    )
    (net (code "79") (name "REG_R2_LEFT_SHIFTED_A") (class "Default")
      (node (ref "CMP13") (pin "P$1") (pinfunction "IN_P$1") (pintype "input"))
      (node (ref "CMP6") (pin "OUT_A") (pinfunction "A_OUT_A") (pintype "output"))
    )
    (net (code "80") (name "REG_R2_LEFT_SHIFTED_B") (class "Default")
      (node (ref "CMP36") (pin "PORT0") (pinfunction "PORT0_PORT0") (pintype "input"))
      (node (ref "CMP6") (pin "OUTB") (pinfunction "B_OUTB") (pintype "output"))
    )
    (net (code "81") (name "REG_R3") (class "Default")
      (node (ref "CMP4") (pin "SRC") (pinfunction "SRC_SRC") (pintype "input"))
      (node (ref "CMP45") (pin "OUT") (pinfunction "OUT_OUT") (pintype "output"))
    )
    (net (code "82") (name "WN_0") (class "Default")
      (node (ref "CMP14") (pin "PORT0") (pinfunction "PORT0_PORT0") (pintype "input"))
      (node (ref "CMP2") (pin "1") (pinfunction "1_1") (pintype "output"))
    )
    (net (code "83") (name "WN_1") (class "Default")
      (node (ref "CMP2") (pin "2") (pinfunction "2_2") (pintype "output"))
      (node (ref "CMP26") (pin "PORT0") (pinfunction "PORT0_PORT0") (pintype "input"))
    )
    (net (code "84") (name "WN_2") (class "Default")
      (node (ref "CMP2") (pin "4") (pinfunction "4_4") (pintype "output"))
      (node (ref "CMP36") (pin "PORT2") (pinfunction "PORT2_PORT2") (pintype "input"))
    )
    (net (code "85") (name "WN_3") (class "Default")
      (node (ref "CMP1") (pin "OUT_A") (pinfunction "A_OUT_A") (pintype "output"))
      (node (ref "CMP40") (pin "PORT2") (pinfunction "PORT2_PORT2") (pintype "input"))
    )
    (net (code "86") (name "WN_3_X") (class "Default")
      (node (ref "CMP1") (pin "INPUT") (pinfunction "IN_INPUT") (pintype "input"))
      (node (ref "CMP2") (pin "3") (pinfunction "3_3") (pintype "output"))
    )
    (net (code "87") (name "WN_4") (class "Default")
      (node (ref "CMP1") (pin "OUTB") (pinfunction "B_OUTB") (pintype "output"))
      (node (ref "CMP12") (pin "RSRC") (pinfunction "SRC_RSRC") (pintype "input"))
    )
    (net (code "88") (name "unconnected-(CMP2-PadSRC)") (class "Default")
      (node (ref "CMP2") (pin "SRC") (pinfunction "SRC_SRC") (pintype "input"))
    )
    (net (code "89") (name "unconnected-(CMP3-PadSRC)") (class "Default")
      (node (ref "CMP3") (pin "SRC") (pinfunction "SRC_SRC") (pintype "input"))
    )
    (net (code "90") (name "unconnected-(CMP4-Pad3)") (class "Default")
      (node (ref "CMP4") (pin "3") (pinfunction "3_3") (pintype "output"))
    )
    (net (code "91") (name "unconnected-(CMP5-OUT_1-PadP$2)") (class "Default")
      (node (ref "CMP5") (pin "P$2") (pinfunction "OUT_1_P$2") (pintype "output"))
    )
    (net (code "92") (name "unconnected-(CMP5-OUT_2-PadP$3)") (class "Default")
      (node (ref "CMP5") (pin "P$3") (pinfunction "OUT_2_P$3") (pintype "output"))
    )
    (net (code "93") (name "unconnected-(CMP5-OUT_3-PadP$4)") (class "Default")
      (node (ref "CMP5") (pin "P$4") (pinfunction "OUT_3_P$4") (pintype "output"))
    )
    (net (code "94") (name "unconnected-(CMP5-OUT_4-PadP$5)") (class "Default")
      (node (ref "CMP5") (pin "P$5") (pinfunction "OUT_4_P$5") (pintype "output"))
    )
    (net (code "95") (name "unconnected-(CMP5-OUT_5-PadP$6)") (class "Default")
      (node (ref "CMP5") (pin "P$6") (pinfunction "OUT_5_P$6") (pintype "output"))
    )
    (net (code "96") (name "unconnected-(CMP5-OUT_6-PadP$7)") (class "Default")
      (node (ref "CMP5") (pin "P$7") (pinfunction "OUT_6_P$7") (pintype "output"))
    )
    (net (code "97") (name "unconnected-(CMP5-OUT_7-PadP$8)") (class "Default")
      (node (ref "CMP5") (pin "P$8") (pinfunction "OUT_7_P$8") (pintype "output"))
    )
    (net (code "98") (name "unconnected-(CMP5-OUT_8-PadP$9)") (class "Default")
      (node (ref "CMP5") (pin "P$9") (pinfunction "OUT_8_P$9") (pintype "output"))
    )
    (net (code "99") (name "unconnected-(CMP5-OUT_9-PadP$10)") (class "Default")
      (node (ref "CMP5") (pin "P$10") (pinfunction "OUT_9_P$10") (pintype "output"))
    )
    (net (code "100") (name "unconnected-(CMP5-OUT_10-PadP$11)") (class "Default")
      (node (ref "CMP5") (pin "P$11") (pinfunction "OUT_10_P$11") (pintype "output"))
    )
    (net (code "101") (name "unconnected-(CMP5-OUT_11-PadP$12)") (class "Default")
      (node (ref "CMP5") (pin "P$12") (pinfunction "OUT_11_P$12") (pintype "output"))
    )
    (net (code "102") (name "unconnected-(CMP5-OUT_12-PadP$13)") (class "Default")
      (node (ref "CMP5") (pin "P$13") (pinfunction "OUT_12_P$13") (pintype "output"))
    )
    (net (code "103") (name "unconnected-(CMP5-OUT_13-PadP$14)") (class "Default")
      (node (ref "CMP5") (pin "P$14") (pinfunction "OUT_13_P$14") (pintype "output"))
    )
    (net (code "104") (name "unconnected-(CMP5-OUT_14-PadP$15)") (class "Default")
      (node (ref "CMP5") (pin "P$15") (pinfunction "OUT_14_P$15") (pintype "output"))
    )
    (net (code "105") (name "unconnected-(CMP5-OUT_15-PadP$16)") (class "Default")
      (node (ref "CMP5") (pin "P$16") (pinfunction "OUT_15_P$16") (pintype "output"))
    )
    (net (code "106") (name "unconnected-(CMP5-PadINPUT)") (class "Default")
      (node (ref "CMP5") (pin "INPUT") (pinfunction "INPUT_INPUT") (pintype "input"))
    )
    (net (code "107") (name "unconnected-(CMP7-Pad3)") (class "Default")
      (node (ref "CMP7") (pin "3") (pinfunction "3_3") (pintype "output"))
    )
    (net (code "108") (name "unconnected-(CMP9-Pad2)") (class "Default")
      (node (ref "CMP9") (pin "2") (pinfunction "2_2") (pintype "output"))
    )
    (net (code "109") (name "unconnected-(CMP10-Pad4)") (class "Default")
      (node (ref "CMP10") (pin "4") (pinfunction "4_4") (pintype "output"))
    )
    (net (code "110") (name "unconnected-(CMP12-LSB_IN-PadSHIFT_IN)") (class "Default")
      (node (ref "CMP12") (pin "SHIFT_IN") (pinfunction "LSB_IN_SHIFT_IN") (pintype "input"))
    )
    (net (code "111") (name "unconnected-(CMP12-OUT-PadLSRC)") (class "Default")
      (node (ref "CMP12") (pin "LSRC") (pinfunction "OUT_LSRC") (pintype "output"))
    )
    (net (code "112") (name "unconnected-(CMP12-PadLSB)") (class "Default")
      (node (ref "CMP12") (pin "LSB") (pinfunction "LSB_LSB") (pintype "output"))
    )
    (net (code "113") (name "unconnected-(CMP13-OUT-PadP$2)") (class "Default")
      (node (ref "CMP13") (pin "P$2") (pinfunction "OUT_P$2") (pintype "output"))
    )
    (net (code "114") (name "unconnected-(CMP20-LSB_IN-PadSHIFT_IN)") (class "Default")
      (node (ref "CMP20") (pin "SHIFT_IN") (pinfunction "LSB_IN_SHIFT_IN") (pintype "input"))
    )
    (net (code "115") (name "unconnected-(CMP20-PadLSB)") (class "Default")
      (node (ref "CMP20") (pin "LSB") (pinfunction "LSB_LSB") (pintype "output"))
    )
    (net (code "116") (name "unconnected-(CMP23-LSB_IN-PadSHIFT_IN)") (class "Default")
      (node (ref "CMP23") (pin "SHIFT_IN") (pinfunction "LSB_IN_SHIFT_IN") (pintype "input"))
    )
    (net (code "117") (name "unconnected-(CMP23-OUT-PadRSRC)") (class "Default")
      (node (ref "CMP23") (pin "RSRC") (pinfunction "OUT_RSRC") (pintype "output"))
    )
    (net (code "118") (name "unconnected-(CMP23-SRC_MSB-PadMSB)") (class "Default")
      (node (ref "CMP23") (pin "MSB") (pinfunction "SRC_MSB_MSB") (pintype "output"))
    )
  )
)
